# Sheet_1.net
KiCad netlist of a schematic drawn in EasyEDA
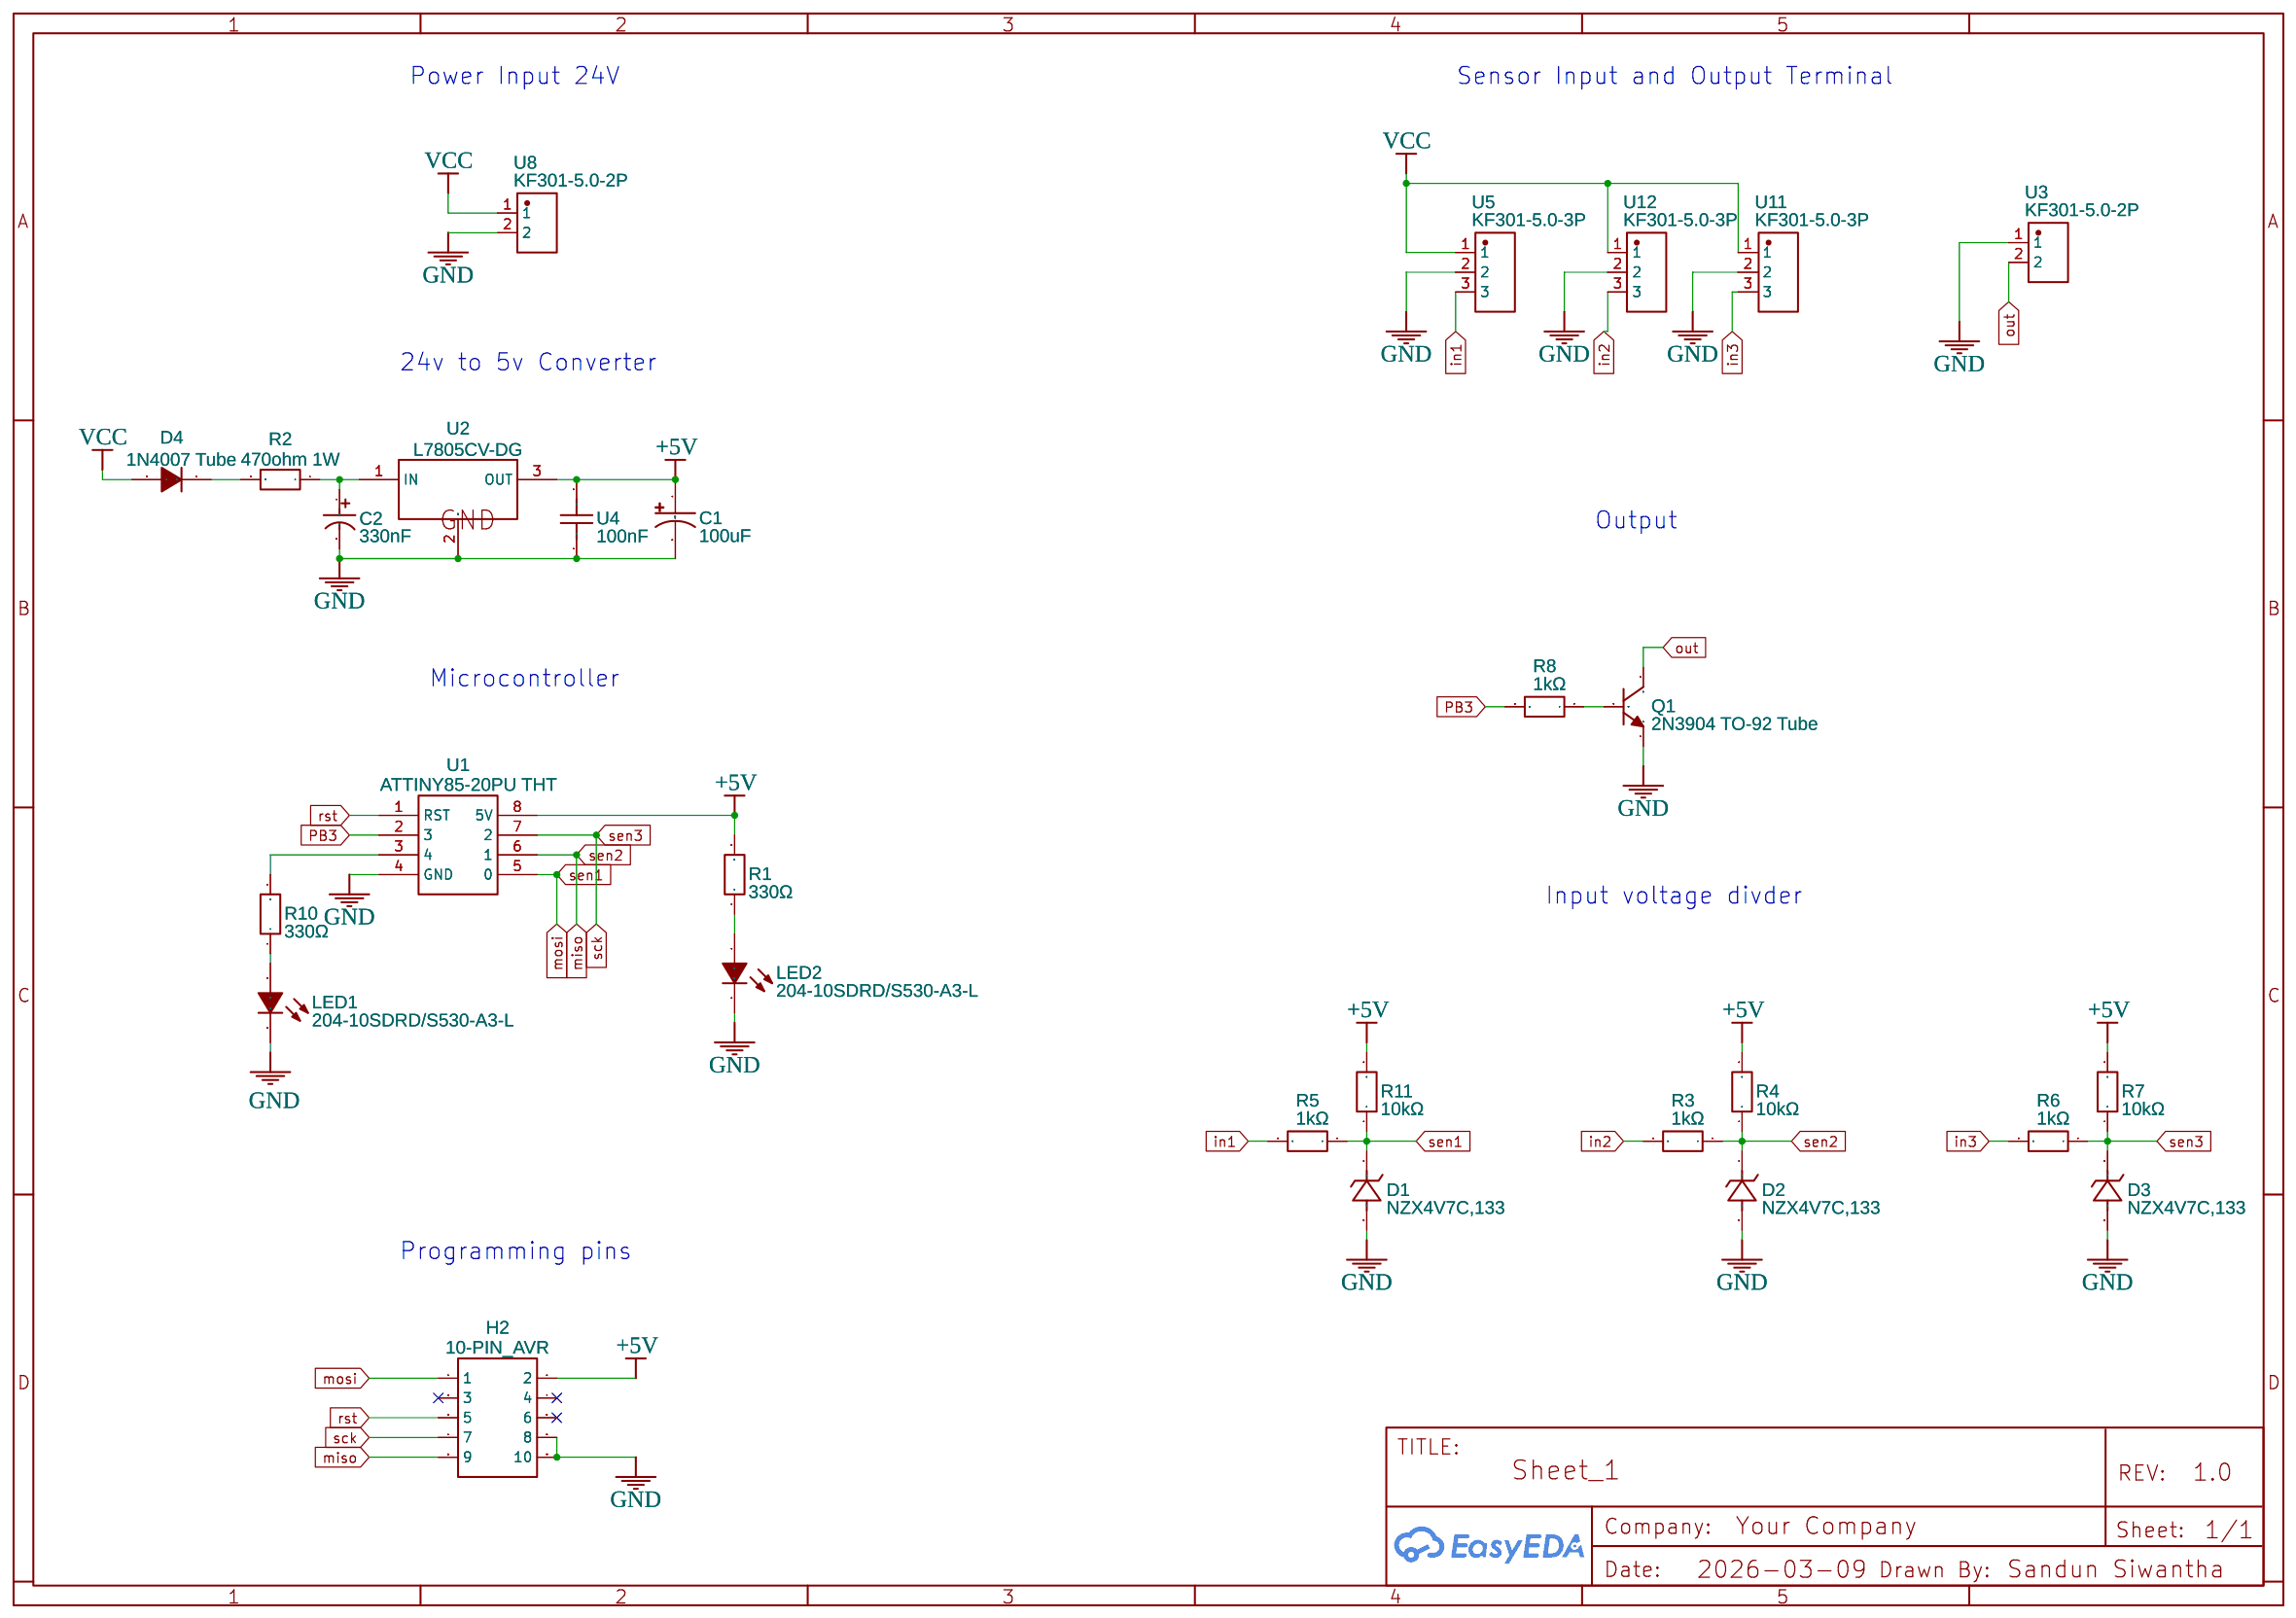
[diagram p0: schematic sheet]

(export (version "E")
  (design (tool "Eeschema 10.0.6"))
  (components
    (comp (ref "C1")
      (value "100uF")
      (fields
        (field (name "Manufacturer Part") "NXA 35V100M 6.3*11")
        (field (name "Manufacturer") "SAMYOUNG(韩国三莹)")
      )
      (libsource (lib "") (part "NXA 35V100uF"))
    )
    (comp (ref "C2")
      (value "330nF")
      (fields
        (field (name "Manufacturer Part") "KM334M050D11RR0VH2FP0")
        (field (name "Manufacturer") "Chengx(承兴)")
      )
      (libsource (lib "") (part "0.33uF 50V 5*11"))
    )
    (comp (ref "D1")
      (value "NZX4V7C,133")
      (fields (field (name "Manufacturer") "Nexperia(安世)"))
      (libsource (lib "") (part "NZX4V7C,133"))
    )
    (comp (ref "D2")
      (value "NZX4V7C,133")
      (fields (field (name "Manufacturer") "Nexperia(安世)"))
      (libsource (lib "") (part "NZX4V7C,133"))
    )
    (comp (ref "D3")
      (value "NZX4V7C,133")
      (fields (field (name "Manufacturer") "Nexperia(安世)"))
      (libsource (lib "") (part "NZX4V7C,133"))
    )
    (comp (ref "D4")
      (value "1N4007 Tube")
      (fields (field (name "Manufacturer Part") "1N4007 编带") (field (name "Manufacturer") "MDD(辰达半导体)"))
      (libsource (lib "") (part "1N4007 Tube"))
    )
    (comp (ref "H2")
      (value "10-PIN_AVR")
      (fields (field (name "Manufacturer Part") "2*5p排针 2.54mm"))
      (libsource (lib "") (part "Header-Male-2.54_2x5"))
    )
    (comp (ref "LED1")
      (value "204-10SDRD/S530-A3-L")
      (fields (field (name "Manufacturer") "EVERLIGHT(亿光)"))
      (libsource (lib "") (part "204-10SDRD/S530-A3-L"))
    )
    (comp (ref "LED2")
      (value "204-10SDRD/S530-A3-L")
      (fields (field (name "Manufacturer") "EVERLIGHT(亿光)"))
      (libsource (lib "") (part "204-10SDRD/S530-A3-L"))
    )
    (comp (ref "Q1")
      (value "2N3904 TO-92 Tube")
      (fields
        (field (name "Manufacturer Part") "2N3904-TA(RANGE:200-300)")
        (field (name "Manufacturer") "CJ(江苏长电/长晶)")
      )
      (libsource (lib "") (part "2N3904 TO-92 Tube"))
    )
    (comp (ref "R1")
      (value "330Ω")
      (fields (field (name "Manufacturer Part") "CR1/4W-330Ω±5%-ST52") (field (name "Manufacturer") "VO(翔胜)"))
      (libsource (lib "") (part "CR1/4W-330Ω±5%-ST52_1"))
    )
    (comp (ref "R2")
      (value "470ohm 1W")
      (fields (field (name "Manufacturer Part") "CR1/4W-330Ω±5%-ST52") (field (name "Manufacturer") "VO(翔胜)"))
      (libsource (lib "") (part "CR1/4W-330Ω±5%-ST52"))
    )
    (comp (ref "R3")
      (value "1kΩ")
      (fields (field (name "Manufacturer Part") "CR1/4W-330Ω±5%-ST52") (field (name "Manufacturer") "VO(翔胜)"))
      (libsource (lib "") (part "CR1/4W-330Ω±5%-ST52"))
    )
    (comp (ref "R4")
      (value "10kΩ")
      (fields (field (name "Manufacturer Part") "CR1/4W-330Ω±5%-ST52") (field (name "Manufacturer") "VO(翔胜)"))
      (libsource (lib "") (part "CR1/4W-330Ω±5%-ST52_1"))
    )
    (comp (ref "R5")
      (value "1kΩ")
      (fields (field (name "Manufacturer Part") "CR1/4W-330Ω±5%-ST52") (field (name "Manufacturer") "VO(翔胜)"))
      (libsource (lib "") (part "CR1/4W-330Ω±5%-ST52"))
    )
    (comp (ref "R6")
      (value "1kΩ")
      (fields (field (name "Manufacturer Part") "CR1/4W-330Ω±5%-ST52") (field (name "Manufacturer") "VO(翔胜)"))
      (libsource (lib "") (part "CR1/4W-330Ω±5%-ST52"))
    )
    (comp (ref "R7")
      (value "10kΩ")
      (fields (field (name "Manufacturer Part") "CR1/4W-330Ω±5%-ST52") (field (name "Manufacturer") "VO(翔胜)"))
      (libsource (lib "") (part "CR1/4W-330Ω±5%-ST52_1"))
    )
    (comp (ref "R8")
      (value "1kΩ")
      (fields (field (name "Manufacturer Part") "CR1/4W-330Ω±5%-ST52") (field (name "Manufacturer") "VO(翔胜)"))
      (libsource (lib "") (part "CR1/4W-330Ω±5%-ST52"))
    )
    (comp (ref "R10")
      (value "330Ω")
      (fields (field (name "Manufacturer Part") "CR1/4W-330Ω±5%-ST52") (field (name "Manufacturer") "VO(翔胜)"))
      (libsource (lib "") (part "CR1/4W-330Ω±5%-ST52_1"))
    )
    (comp (ref "R11")
      (value "10kΩ")
      (fields (field (name "Manufacturer Part") "CR1/4W-330Ω±5%-ST52") (field (name "Manufacturer") "VO(翔胜)"))
      (libsource (lib "") (part "CR1/4W-330Ω±5%-ST52_1"))
    )
    (comp (ref "U1")
      (value "ATTINY85-20PU THT")
      (fields (field (name "Manufacturer Part") "ATTINY85-20PU"))
      (libsource (lib "") (part "ATTINY85-20PU THT"))
    )
    (comp (ref "U2")
      (value "L7805CV-DG")
      (fields (field (name "Manufacturer") "ST(意法半导体)"))
      (libsource (lib "") (part "L7805CV-DG"))
    )
    (comp (ref "U3")
      (value "KF301-5.0-2P")
      (fields (field (name "Manufacturer") "KEFA(科发)"))
      (libsource (lib "") (part "KF301-5.0-2P"))
    )
    (comp (ref "U4")
      (value "100nF")
      (fields
        (field (name "Manufacturer Part") "CC1H104MC1FD3F6C10SA")
        (field (name "Manufacturer") "Dersonic(德尔创)")
      )
      (libsource (lib "") (part "CC1H104MC1FD3F6C10SA"))
    )
    (comp (ref "U5")
      (value "KF301-5.0-3P")
      (fields (field (name "Manufacturer") "KEFA(科发)"))
      (libsource (lib "") (part "KF301-5.0-3P_1"))
    )
    (comp (ref "U8")
      (value "KF301-5.0-2P")
      (fields (field (name "Manufacturer") "KEFA(科发)"))
      (libsource (lib "") (part "KF301-5.0-2P"))
    )
    (comp (ref "U11")
      (value "KF301-5.0-3P")
      (fields (field (name "Manufacturer") "KEFA(科发)"))
      (libsource (lib "") (part "KF301-5.0-3P_2"))
    )
    (comp (ref "U12")
      (value "KF301-5.0-3P")
      (fields (field (name "Manufacturer") "KEFA(科发)"))
      (libsource (lib "") (part "KF301-5.0-3P"))
    )
  )
  (nets
    (net (code "1") (name "+5V") (class "Default")
      (node (ref "C1") (pin "1") (pinfunction "1_1") (pintype "unspecified"))
      (node (ref "H2") (pin "2") (pinfunction "2_2") (pintype "input"))
      (node (ref "R1") (pin "2") (pinfunction "2_2") (pintype "unspecified"))
      (node (ref "R11") (pin "2") (pinfunction "2_2") (pintype "unspecified"))
      (node (ref "R4") (pin "2") (pinfunction "2_2") (pintype "unspecified"))
      (node (ref "R7") (pin "2") (pinfunction "2_2") (pintype "unspecified"))
      (node (ref "U1") (pin "8") (pinfunction "5V_8") (pintype "unspecified"))
      (node (ref "U2") (pin "3") (pinfunction "OUT_3") (pintype "passive"))
      (node (ref "U4") (pin "2") (pinfunction "2_2") (pintype "unspecified"))
    )
    (net (code "2") (name "GND") (class "Default")
      (node (ref "C1") (pin "2") (pinfunction "2_2") (pintype "unspecified"))
      (node (ref "C2") (pin "2") (pinfunction "2_2") (pintype "input"))
      (node (ref "D1") (pin "2") (pinfunction "A_2") (pintype "unspecified"))
      (node (ref "D2") (pin "2") (pinfunction "A_2") (pintype "unspecified"))
      (node (ref "D3") (pin "2") (pinfunction "A_2") (pintype "unspecified"))
      (node (ref "H2") (pin "10") (pinfunction "10_10") (pintype "input"))
      (node (ref "H2") (pin "8") (pinfunction "8_8") (pintype "input"))
      (node (ref "LED1") (pin "2") (pinfunction "C_2") (pintype "input"))
      (node (ref "LED2") (pin "2") (pinfunction "C_2") (pintype "input"))
      (node (ref "Q1") (pin "1") (pinfunction "E_1") (pintype "unspecified"))
      (node (ref "U1") (pin "4") (pinfunction "GND_4") (pintype "unspecified"))
      (node (ref "U11") (pin "2") (pinfunction "2_2") (pintype "unspecified"))
      (node (ref "U12") (pin "2") (pinfunction "2_2") (pintype "unspecified"))
      (node (ref "U2") (pin "2") (pinfunction "GND_2") (pintype "passive"))
      (node (ref "U3") (pin "1") (pinfunction "1_1") (pintype "unspecified"))
      (node (ref "U4") (pin "1") (pinfunction "1_1") (pintype "unspecified"))
      (node (ref "U5") (pin "2") (pinfunction "2_2") (pintype "unspecified"))
      (node (ref "U8") (pin "2") (pinfunction "2_2") (pintype "unspecified"))
    )
    (net (code "3") (name "Net-(D4-K)") (class "Default")
      (node (ref "D4") (pin "1") (pinfunction "K_1") (pintype "unspecified"))
      (node (ref "R2") (pin "2") (pinfunction "2_2") (pintype "unspecified"))
    )
    (net (code "4") (name "Net-(LED1-A)") (class "Default")
      (node (ref "LED1") (pin "1") (pinfunction "A_1") (pintype "input"))
      (node (ref "R10") (pin "1") (pinfunction "1_1") (pintype "unspecified"))
    )
    (net (code "5") (name "Net-(LED2-A)") (class "Default")
      (node (ref "LED2") (pin "1") (pinfunction "A_1") (pintype "input"))
      (node (ref "R1") (pin "1") (pinfunction "1_1") (pintype "unspecified"))
    )
    (net (code "6") (name "Net-(Q1-B)") (class "Default")
      (node (ref "Q1") (pin "2") (pinfunction "B_2") (pintype "unspecified"))
      (node (ref "R8") (pin "1") (pinfunction "1_1") (pintype "unspecified"))
    )
    (net (code "7") (name "Net-(U1-4)") (class "Default")
      (node (ref "R10") (pin "2") (pinfunction "2_2") (pintype "unspecified"))
      (node (ref "U1") (pin "3") (pinfunction "4_3") (pintype "unspecified"))
    )
    (net (code "8") (name "Net-(U2-IN)") (class "Default")
      (node (ref "C2") (pin "1") (pinfunction "1_1") (pintype "input"))
      (node (ref "R2") (pin "1") (pinfunction "1_1") (pintype "unspecified"))
      (node (ref "U2") (pin "1") (pinfunction "IN_1") (pintype "passive"))
    )
    (net (code "9") (name "PB3") (class "Default")
      (node (ref "R8") (pin "2") (pinfunction "2_2") (pintype "unspecified"))
      (node (ref "U1") (pin "2") (pinfunction "3_2") (pintype "unspecified"))
    )
    (net (code "10") (name "VCC") (class "Default")
      (node (ref "D4") (pin "2") (pinfunction "A_2") (pintype "unspecified"))
      (node (ref "U11") (pin "1") (pinfunction "1_1") (pintype "unspecified"))
      (node (ref "U12") (pin "1") (pinfunction "1_1") (pintype "unspecified"))
      (node (ref "U5") (pin "1") (pinfunction "1_1") (pintype "unspecified"))
      (node (ref "U8") (pin "1") (pinfunction "1_1") (pintype "unspecified"))
    )
    (net (code "11") (name "in1") (class "Default")
      (node (ref "R5") (pin "2") (pinfunction "2_2") (pintype "unspecified"))
      (node (ref "U5") (pin "3") (pinfunction "3_3") (pintype "unspecified"))
    )
    (net (code "12") (name "in2") (class "Default")
      (node (ref "R3") (pin "2") (pinfunction "2_2") (pintype "unspecified"))
      (node (ref "U12") (pin "3") (pinfunction "3_3") (pintype "unspecified"))
    )
    (net (code "13") (name "in3") (class "Default")
      (node (ref "R6") (pin "2") (pinfunction "2_2") (pintype "unspecified"))
      (node (ref "U11") (pin "3") (pinfunction "3_3") (pintype "unspecified"))
    )
    (net (code "14") (name "miso") (class "Default")
      (node (ref "D2") (pin "1") (pinfunction "K_1") (pintype "unspecified"))
      (node (ref "H2") (pin "9") (pinfunction "9_9") (pintype "input"))
      (node (ref "R3") (pin "1") (pinfunction "1_1") (pintype "unspecified"))
      (node (ref "R4") (pin "1") (pinfunction "1_1") (pintype "unspecified"))
      (node (ref "U1") (pin "6") (pinfunction "1_6") (pintype "unspecified"))
    )
    (net (code "15") (name "mosi") (class "Default")
      (node (ref "D1") (pin "1") (pinfunction "K_1") (pintype "unspecified"))
      (node (ref "H2") (pin "1") (pinfunction "1_1") (pintype "input"))
      (node (ref "R11") (pin "1") (pinfunction "1_1") (pintype "unspecified"))
      (node (ref "R5") (pin "1") (pinfunction "1_1") (pintype "unspecified"))
      (node (ref "U1") (pin "5") (pinfunction "0_5") (pintype "unspecified"))
    )
    (net (code "16") (name "out") (class "Default")
      (node (ref "Q1") (pin "3") (pinfunction "C_3") (pintype "unspecified"))
      (node (ref "U3") (pin "2") (pinfunction "2_2") (pintype "unspecified"))
    )
    (net (code "17") (name "rst") (class "Default")
      (node (ref "H2") (pin "5") (pinfunction "5_5") (pintype "input"))
      (node (ref "U1") (pin "1") (pinfunction "RST_1") (pintype "unspecified"))
    )
    (net (code "18") (name "sck") (class "Default")
      (node (ref "D3") (pin "1") (pinfunction "K_1") (pintype "unspecified"))
      (node (ref "H2") (pin "7") (pinfunction "7_7") (pintype "input"))
      (node (ref "R6") (pin "1") (pinfunction "1_1") (pintype "unspecified"))
      (node (ref "R7") (pin "1") (pinfunction "1_1") (pintype "unspecified"))
      (node (ref "U1") (pin "7") (pinfunction "2_7") (pintype "unspecified"))
    )
    (net (code "19") (name "unconnected-(H2-Pad3)") (class "Default")
      (node (ref "H2") (pin "3") (pinfunction "3_3") (pintype "input+no_connect"))
    )
    (net (code "20") (name "unconnected-(H2-Pad4)") (class "Default")
      (node (ref "H2") (pin "4") (pinfunction "4_4") (pintype "input+no_connect"))
    )
    (net (code "21") (name "unconnected-(H2-Pad6)") (class "Default")
      (node (ref "H2") (pin "6") (pinfunction "6_6") (pintype "input+no_connect"))
    )
  )
)
